# Task.net
KiCad netlist of a schematic drawn in Altium Designer
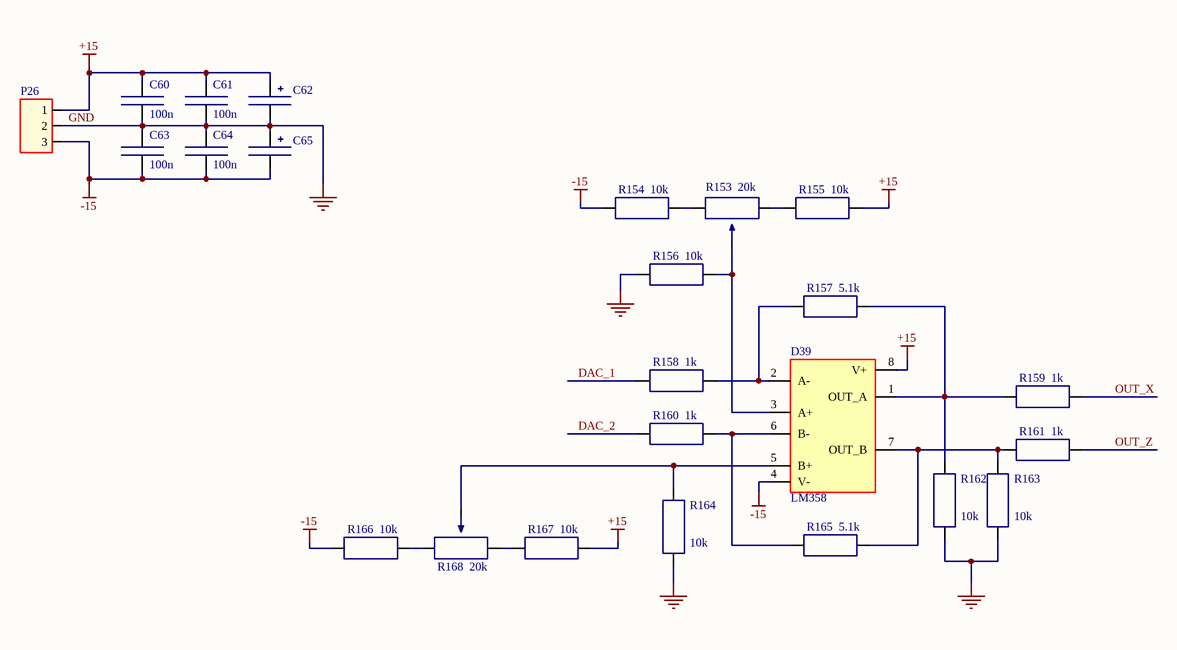
[diagram p0: Task.SchDoc]

(export (version "E")
  (design (tool "Eeschema 10.0.6"))
  (components
    (comp (ref "C60") (value "100n") (footprint "C0805") (libsource (lib "Library") (part "C0805")))
    (comp (ref "C61") (value "100n") (footprint "C0805") (libsource (lib "Library") (part "C0805")))
    (comp (ref "C62")
      (value "Capacitor_Polyar")
      (footprint "Library:SMD_El_SizeA")
      (libsource (lib "Library") (part "Capacitor_Polyar"))
    )
    (comp (ref "C63") (value "100n") (footprint "C0805") (libsource (lib "Library") (part "C0805")))
    (comp (ref "C64") (value "100n") (footprint "C0805") (libsource (lib "Library") (part "C0805")))
    (comp (ref "C65")
      (value "Capacitor_Polyar")
      (footprint "Library:SMD_El_SizeA")
      (libsource (lib "Library") (part "Capacitor_Polyar"))
    )
    (comp (ref "D39") (value "LM358") (footprint "SOIC-8") (libsource (lib "Library") (part "LM358")))
    (comp (ref "P26")
      (value "KLS_3_5mm")
      (footprint "KLS_3_5MM")
      (libsource (lib "Library") (part "KLS_3_5mm"))
    )
    (comp (ref "R153") (value "20k") (footprint "RES_POT_1") (libsource (lib "Library") (part "Res_Pot_1")))
    (comp (ref "R154") (value "10k") (footprint "R0805") (libsource (lib "Library") (part "R0805")))
    (comp (ref "R155") (value "10k") (footprint "R0805") (libsource (lib "Library") (part "R0805")))
    (comp (ref "R156") (value "10k") (footprint "R0805") (libsource (lib "Library") (part "R0805")))
    (comp (ref "R157") (value "5.1k") (footprint "R0805") (libsource (lib "Library") (part "R0805")))
    (comp (ref "R158") (value "1k") (footprint "R0805") (libsource (lib "Library") (part "R0805")))
    (comp (ref "R159") (value "1k") (footprint "R0805") (libsource (lib "Library") (part "R0805")))
    (comp (ref "R160") (value "1k") (footprint "R0805") (libsource (lib "Library") (part "R0805")))
    (comp (ref "R161") (value "1k") (footprint "R0805") (libsource (lib "Library") (part "R0805")))
    (comp (ref "R162") (value "10k") (footprint "R0805") (libsource (lib "Library") (part "R0805")))
    (comp (ref "R163") (value "10k") (footprint "R0805") (libsource (lib "Library") (part "R0805")))
    (comp (ref "R164") (value "10k") (footprint "R0805") (libsource (lib "Library") (part "R0805")))
    (comp (ref "R165") (value "5.1k") (footprint "R0805") (libsource (lib "Library") (part "R0805")))
    (comp (ref "R166") (value "10k") (footprint "R0805") (libsource (lib "Library") (part "R0805")))
    (comp (ref "R167") (value "10k") (footprint "R0805") (libsource (lib "Library") (part "R0805")))
    (comp (ref "R168") (value "20k") (footprint "RES_POT_1") (libsource (lib "Library") (part "Res_Pot_1")))
  )
  (nets
    (net (code "1") (name "+15") (class "Default")
      (node (ref "C60") (pin "1") (pinfunction "1_1") (pintype "passive"))
      (node (ref "C61") (pin "1") (pinfunction "1_1") (pintype "passive"))
      (node (ref "C62") (pin "1") (pinfunction "1_1") (pintype "passive"))
      (node (ref "D39") (pin "8") (pinfunction "V+_8") (pintype "passive"))
      (node (ref "P26") (pin "1") (pinfunction "1_1") (pintype "passive"))
      (node (ref "R155") (pin "1") (pinfunction "1_1") (pintype "passive"))
      (node (ref "R167") (pin "1") (pinfunction "1_1") (pintype "passive"))
    )
    (net (code "2") (name "-15") (class "Default")
      (node (ref "C63") (pin "2") (pinfunction "2_2") (pintype "passive"))
      (node (ref "C64") (pin "2") (pinfunction "2_2") (pintype "passive"))
      (node (ref "C65") (pin "2") (pinfunction "2_2") (pintype "passive"))
      (node (ref "D39") (pin "4") (pinfunction "V-_4") (pintype "passive"))
      (node (ref "P26") (pin "3") (pinfunction "3_3") (pintype "passive"))
      (node (ref "R154") (pin "2") (pinfunction "2_2") (pintype "passive"))
      (node (ref "R166") (pin "2") (pinfunction "2_2") (pintype "passive"))
    )
    (net (code "3") (name "/DAC_1") (class "Default")
      (node (ref "R158") (pin "2") (pinfunction "2_2") (pintype "passive"))
    )
    (net (code "4") (name "/DAC_2") (class "Default")
      (node (ref "R160") (pin "2") (pinfunction "2_2") (pintype "passive"))
    )
    (net (code "5") (name "/OUT_X") (class "Default")
      (node (ref "R159") (pin "1") (pinfunction "1_1") (pintype "passive"))
    )
    (net (code "6") (name "/OUT_Z") (class "Default")
      (node (ref "R161") (pin "1") (pinfunction "1_1") (pintype "passive"))
    )
    (net (code "7") (name "GND") (class "Default")
      (node (ref "C60") (pin "2") (pinfunction "2_2") (pintype "passive"))
      (node (ref "C61") (pin "2") (pinfunction "2_2") (pintype "passive"))
      (node (ref "C62") (pin "2") (pinfunction "2_2") (pintype "passive"))
      (node (ref "C63") (pin "1") (pinfunction "1_1") (pintype "passive"))
      (node (ref "C64") (pin "1") (pinfunction "1_1") (pintype "passive"))
      (node (ref "C65") (pin "1") (pinfunction "1_1") (pintype "passive"))
      (node (ref "P26") (pin "2") (pinfunction "2_2") (pintype "passive"))
      (node (ref "R156") (pin "2") (pinfunction "2_2") (pintype "passive"))
      (node (ref "R162") (pin "1") (pinfunction "1_1") (pintype "passive"))
      (node (ref "R163") (pin "1") (pinfunction "1_1") (pintype "passive"))
      (node (ref "R164") (pin "2") (pinfunction "2_2") (pintype "passive"))
    )
    (net (code "8") (name "Net-(D39-A+)") (class "Default")
      (node (ref "D39") (pin "3") (pinfunction "A+_3") (pintype "passive"))
      (node (ref "R153") (pin "3") (pinfunction "3_3") (pintype "passive"))
      (node (ref "R156") (pin "1") (pinfunction "1_1") (pintype "passive"))
    )
    (net (code "9") (name "Net-(D39-A-)") (class "Default")
      (node (ref "D39") (pin "2") (pinfunction "A-_2") (pintype "passive"))
      (node (ref "R157") (pin "2") (pinfunction "2_2") (pintype "passive"))
      (node (ref "R158") (pin "1") (pinfunction "1_1") (pintype "passive"))
    )
    (net (code "10") (name "Net-(D39-B+)") (class "Default")
      (node (ref "D39") (pin "5") (pinfunction "B+_5") (pintype "passive"))
      (node (ref "R164") (pin "1") (pinfunction "1_1") (pintype "passive"))
      (node (ref "R168") (pin "3") (pinfunction "3_3") (pintype "passive"))
    )
    (net (code "11") (name "Net-(D39-B-)") (class "Default")
      (node (ref "D39") (pin "6") (pinfunction "B-_6") (pintype "passive"))
      (node (ref "R160") (pin "1") (pinfunction "1_1") (pintype "passive"))
      (node (ref "R165") (pin "2") (pinfunction "2_2") (pintype "passive"))
    )
    (net (code "12") (name "Net-(D39-OUT_A)") (class "Default")
      (node (ref "D39") (pin "1") (pinfunction "OUT_A_1") (pintype "passive"))
      (node (ref "R157") (pin "1") (pinfunction "1_1") (pintype "passive"))
      (node (ref "R159") (pin "2") (pinfunction "2_2") (pintype "passive"))
      (node (ref "R162") (pin "2") (pinfunction "2_2") (pintype "passive"))
    )
    (net (code "13") (name "Net-(D39-OUT_B)") (class "Default")
      (node (ref "D39") (pin "7") (pinfunction "OUT_B_7") (pintype "passive"))
      (node (ref "R161") (pin "2") (pinfunction "2_2") (pintype "passive"))
      (node (ref "R163") (pin "2") (pinfunction "2_2") (pintype "passive"))
      (node (ref "R165") (pin "1") (pinfunction "1_1") (pintype "passive"))
    )
    (net (code "14") (name "Net-(R153-Pad1)") (class "Default")
      (node (ref "R153") (pin "1") (pinfunction "1_1") (pintype "passive"))
      (node (ref "R155") (pin "2") (pinfunction "2_2") (pintype "passive"))
    )
    (net (code "15") (name "Net-(R153-Pad2)") (class "Default")
      (node (ref "R153") (pin "2") (pinfunction "2_2") (pintype "passive"))
      (node (ref "R154") (pin "1") (pinfunction "1_1") (pintype "passive"))
    )
    (net (code "16") (name "Net-(R166-Pad1)") (class "Default")
      (node (ref "R166") (pin "1") (pinfunction "1_1") (pintype "passive"))
      (node (ref "R168") (pin "1") (pinfunction "1_1") (pintype "passive"))
    )
    (net (code "17") (name "Net-(R167-Pad2)") (class "Default")
      (node (ref "R167") (pin "2") (pinfunction "2_2") (pintype "passive"))
      (node (ref "R168") (pin "2") (pinfunction "2_2") (pintype "passive"))
    )
  )
)
